# WizFiShield.net
KiCad netlist of a schematic drawn in EAGLE
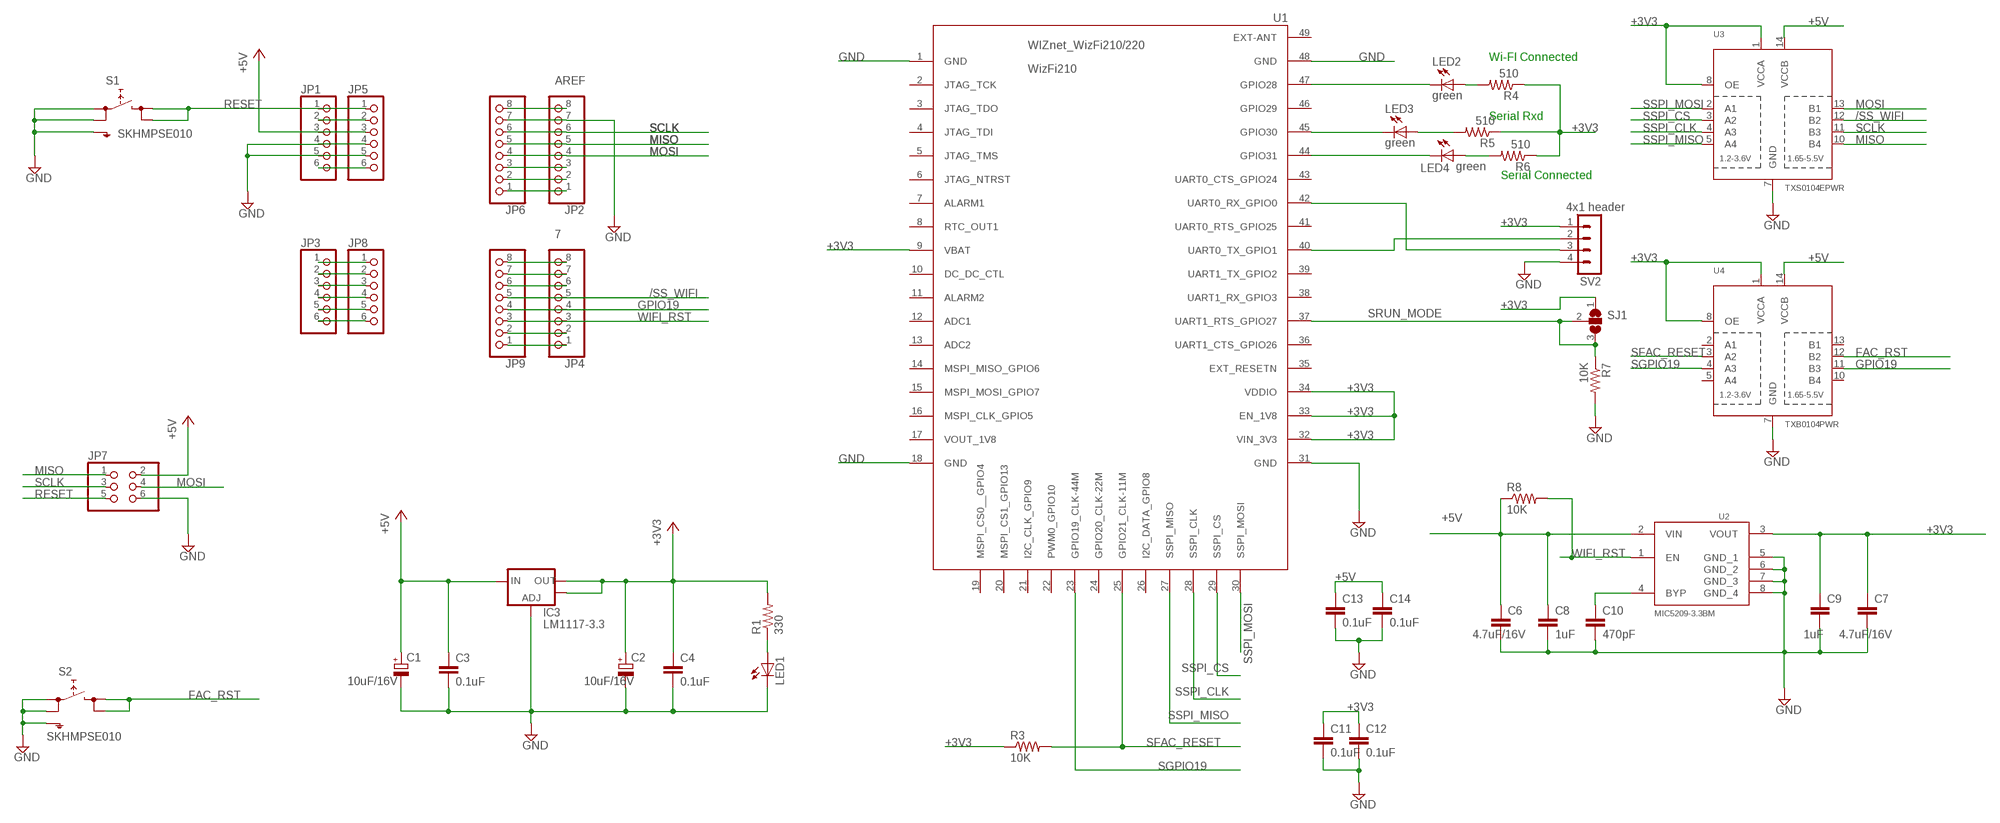
[diagram p0: schematic, sheet 1]

(export (version "E")
  (design (tool "Eeschema 10.0.6"))
  (components
    (comp (ref "C1")
      (value "10uF/16V")
      (footprint "eagle-import:CT3216")
      (libsource (lib "eagle-import") (part "CPOL-EUCT3216"))
    )
    (comp (ref "C2")
      (value "10uF/16V")
      (footprint "eagle-import:CT3216")
      (libsource (lib "eagle-import") (part "CPOL-EUCT3216"))
    )
    (comp (ref "C3")
      (value "0.1uF")
      (footprint "eagle-import:C0603")
      (libsource (lib "eagle-import") (part "C-EUC0603"))
    )
    (comp (ref "C4")
      (value "0.1uF")
      (footprint "eagle-import:C0603")
      (libsource (lib "eagle-import") (part "C-EUC0603"))
    )
    (comp (ref "C6")
      (value "4.7uF/16V")
      (footprint "eagle-import:C0805")
      (libsource (lib "eagle-import") (part "C-EUC0805"))
    )
    (comp (ref "C7")
      (value "4.7uF/16V")
      (footprint "eagle-import:C0603")
      (libsource (lib "eagle-import") (part "C-EUC0603"))
    )
    (comp (ref "C8")
      (value "1uF")
      (footprint "eagle-import:C0603")
      (libsource (lib "eagle-import") (part "C-EUC0603"))
    )
    (comp (ref "C9")
      (value "1uF")
      (footprint "eagle-import:C0805")
      (libsource (lib "eagle-import") (part "C-EUC0805"))
    )
    (comp (ref "C10")
      (value "470pF")
      (footprint "eagle-import:C0603")
      (libsource (lib "eagle-import") (part "C-EUC0603"))
    )
    (comp (ref "C11")
      (value "0.1uF")
      (footprint "eagle-import:C0603")
      (libsource (lib "eagle-import") (part "C-EUC0603"))
    )
    (comp (ref "C12")
      (value "0.1uF")
      (footprint "eagle-import:C0603")
      (libsource (lib "eagle-import") (part "C-EUC0603"))
    )
    (comp (ref "C13")
      (value "0.1uF")
      (footprint "eagle-import:C0603")
      (libsource (lib "eagle-import") (part "C-EUC0603"))
    )
    (comp (ref "C14")
      (value "0.1uF")
      (footprint "eagle-import:C0603")
      (libsource (lib "eagle-import") (part "C-EUC0603"))
    )
    (comp (ref "IC3")
      (value "LM1117-3.3")
      (footprint "eagle-import:SOT223")
      (libsource (lib "eagle-import") (part "V_REG_LM1117SOT223"))
    )
    (comp (ref "JP1")
      (value "PINHD-1X6")
      (footprint "eagle-import:1X06")
      (libsource (lib "eagle-import") (part "PINHD-1X6"))
    )
    (comp (ref "JP2")
      (value "PINHD-1X8")
      (footprint "eagle-import:1X08")
      (libsource (lib "eagle-import") (part "PINHD-1X8"))
    )
    (comp (ref "JP3")
      (value "PINHD-1X6")
      (footprint "eagle-import:1X06")
      (libsource (lib "eagle-import") (part "PINHD-1X6"))
    )
    (comp (ref "JP4")
      (value "PINHD-1X8")
      (footprint "eagle-import:1X08")
      (libsource (lib "eagle-import") (part "PINHD-1X8"))
    )
    (comp (ref "JP5")
      (value "PINHD-1X6")
      (footprint "eagle-import:1X06")
      (libsource (lib "eagle-import") (part "PINHD-1X6"))
    )
    (comp (ref "JP6")
      (value "PINHD-1X8")
      (footprint "eagle-import:1X08")
      (libsource (lib "eagle-import") (part "PINHD-1X8"))
    )
    (comp (ref "JP7")
      (value "PINHD-2X3")
      (footprint "eagle-import:2X03")
      (libsource (lib "eagle-import") (part "PINHD-2X3"))
    )
    (comp (ref "JP8")
      (value "PINHD-1X6")
      (footprint "eagle-import:1X06")
      (libsource (lib "eagle-import") (part "PINHD-1X6"))
    )
    (comp (ref "JP9")
      (value "PINHD-1X8")
      (footprint "eagle-import:1X08")
      (libsource (lib "eagle-import") (part "PINHD-1X8"))
    )
    (comp (ref "LED1")
      (value "LEDCHIP-LED0805")
      (footprint "eagle-import:CHIP-LED0805")
      (libsource (lib "eagle-import") (part "led_LEDCHIP-LED0805"))
    )
    (comp (ref "LED2")
      (value "green")
      (footprint "eagle-import:CHIP-LED0805")
      (libsource (lib "eagle-import") (part "LEDCHIP-LED0805"))
    )
    (comp (ref "LED3")
      (value "green")
      (footprint "eagle-import:CHIP-LED0805")
      (libsource (lib "eagle-import") (part "LEDCHIP-LED0805"))
    )
    (comp (ref "LED4")
      (value "green")
      (footprint "eagle-import:CHIP-LED0805")
      (libsource (lib "eagle-import") (part "LEDCHIP-LED0805"))
    )
    (comp (ref "R1")
      (value "330")
      (footprint "eagle-import:R0805")
      (libsource (lib "eagle-import") (part "R-US_R0805"))
    )
    (comp (ref "R3")
      (value "10K")
      (footprint "eagle-import:0603-RES")
      (libsource (lib "eagle-import") (part "RESISTOR0603-RES"))
    )
    (comp (ref "R4")
      (value "510")
      (footprint "eagle-import:0603-RES")
      (libsource (lib "eagle-import") (part "RESISTOR0603-RES"))
    )
    (comp (ref "R5")
      (value "510")
      (footprint "eagle-import:0603-RES")
      (libsource (lib "eagle-import") (part "RESISTOR0603-RES"))
    )
    (comp (ref "R6")
      (value "510")
      (footprint "eagle-import:0603-RES")
      (libsource (lib "eagle-import") (part "RESISTOR0603-RES"))
    )
    (comp (ref "R7")
      (value "10K")
      (footprint "eagle-import:0603-RES")
      (libsource (lib "eagle-import") (part "RESISTOR0603-RES"))
    )
    (comp (ref "R8")
      (value "10K")
      (footprint "eagle-import:0603-RES")
      (libsource (lib "eagle-import") (part "RESISTOR0603-RES"))
    )
    (comp (ref "S1")
      (value "SKHMPSE010")
      (footprint "eagle-import:SKHMPXE010")
      (libsource (lib "eagle-import") (part "SKHMPE010S"))
    )
    (comp (ref "S2")
      (value "SKHMPSE010")
      (footprint "eagle-import:SKHMPXE010")
      (libsource (lib "eagle-import") (part "SKHMPE010S"))
    )
    (comp (ref "SJ1")
      (value "SJ2W")
      (footprint "eagle-import:SJ_2")
      (libsource (lib "eagle-import") (part "SJ2W"))
    )
    (comp (ref "SV2")
      (value "4x1 header")
      (footprint "eagle-import:MA04-1")
      (libsource (lib "eagle-import") (part "MA04-1"))
    )
    (comp (ref "U1")
      (value "WizFi210")
      (footprint "eagle-import:WIZFI210_220")
      (libsource (lib "eagle-import") (part "WIZFI210/220"))
    )
    (comp (ref "U2")
      (value "MIC5209-3.3BM")
      (footprint "eagle-import:SO08")
      (libsource (lib "eagle-import") (part "MIC5209"))
    )
    (comp (ref "U3")
      (value "TXS0104EPWR")
      (footprint "eagle-import:TSSOP14")
      (libsource (lib "eagle-import") (part "TXB0104PWR"))
    )
    (comp (ref "U4")
      (value "TXB0104PWR")
      (footprint "eagle-import:TSSOP14")
      (libsource (lib "eagle-import") (part "TXB0104PWR"))
    )
  )
  (nets
    (net (code "1") (name "+3V3") (class "Default")
      (node (ref "C11") (pin "1") (pinfunction "1_1") (pintype "passive"))
      (node (ref "C12") (pin "1") (pinfunction "1_1") (pintype "passive"))
      (node (ref "C2") (pin "+") (pinfunction "+_+") (pintype "passive"))
      (node (ref "C4") (pin "1") (pinfunction "1_1") (pintype "passive"))
      (node (ref "C7") (pin "1") (pinfunction "1_1") (pintype "passive"))
      (node (ref "C9") (pin "1") (pinfunction "1_1") (pintype "passive"))
      (node (ref "IC3") (pin "2") (pinfunction "OUT_2") (pintype "output"))
      (node (ref "IC3") (pin "4") (pinfunction "OUT_4") (pintype "output"))
      (node (ref "R1") (pin "2") (pinfunction "2_2") (pintype "passive"))
      (node (ref "R3") (pin "1") (pinfunction "1_1") (pintype "passive"))
      (node (ref "R4") (pin "1") (pinfunction "1_1") (pintype "passive"))
      (node (ref "R5") (pin "1") (pinfunction "1_1") (pintype "passive"))
      (node (ref "R6") (pin "1") (pinfunction "1_1") (pintype "passive"))
      (node (ref "SJ1") (pin "1") (pinfunction "1_1") (pintype "passive"))
      (node (ref "SV2") (pin "1") (pinfunction "1_1") (pintype "passive"))
      (node (ref "U1") (pin "32") (pinfunction "VIN_3V3_32") (pintype "power_in"))
      (node (ref "U1") (pin "33") (pinfunction "EN_1V8_33") (pintype "input"))
      (node (ref "U1") (pin "34") (pinfunction "VDDIO_34") (pintype "power_in"))
      (node (ref "U1") (pin "9") (pinfunction "VBAT_9") (pintype "power_in"))
      (node (ref "U2") (pin "3") (pinfunction "VOUT_3") (pintype "output"))
      (node (ref "U3") (pin "1") (pinfunction "VCCA_1") (pintype "bidirectional"))
      (node (ref "U3") (pin "8") (pinfunction "OE_8") (pintype "bidirectional"))
      (node (ref "U4") (pin "1") (pinfunction "VCCA_1") (pintype "bidirectional"))
      (node (ref "U4") (pin "8") (pinfunction "OE_8") (pintype "bidirectional"))
    )
    (net (code "2") (name "+5V") (class "Default")
      (node (ref "C1") (pin "+") (pinfunction "+_+") (pintype "passive"))
      (node (ref "C13") (pin "1") (pinfunction "1_1") (pintype "passive"))
      (node (ref "C14") (pin "1") (pinfunction "1_1") (pintype "passive"))
      (node (ref "C3") (pin "1") (pinfunction "1_1") (pintype "passive"))
      (node (ref "C6") (pin "1") (pinfunction "1_1") (pintype "passive"))
      (node (ref "C8") (pin "1") (pinfunction "1_1") (pintype "passive"))
      (node (ref "IC3") (pin "3") (pinfunction "IN_3") (pintype "input"))
      (node (ref "JP1") (pin "3") (pinfunction "3_3") (pintype "passive"))
      (node (ref "JP5") (pin "3") (pinfunction "3_3") (pintype "passive"))
      (node (ref "JP7") (pin "2") (pinfunction "2_2") (pintype "passive"))
      (node (ref "R8") (pin "1") (pinfunction "1_1") (pintype "passive"))
      (node (ref "U2") (pin "2") (pinfunction "VIN_2") (pintype "input"))
      (node (ref "U3") (pin "14") (pinfunction "VCCB_14") (pintype "bidirectional"))
      (node (ref "U4") (pin "14") (pinfunction "VCCB_14") (pintype "bidirectional"))
    )
    (net (code "3") (name "/FAC_RST") (class "Default")
      (node (ref "S2") (pin "3") (pinfunction "2.1_3") (pintype "passive"))
      (node (ref "S2") (pin "4") (pinfunction "2.2_4") (pintype "passive"))
      (node (ref "U4") (pin "12") (pinfunction "B2_12") (pintype "bidirectional"))
    )
    (net (code "4") (name "/GPIO19") (class "Default")
      (node (ref "JP4") (pin "4") (pinfunction "4_4") (pintype "passive"))
      (node (ref "JP9") (pin "4") (pinfunction "4_4") (pintype "passive"))
      (node (ref "U4") (pin "11") (pinfunction "B3_11") (pintype "bidirectional"))
    )
    (net (code "5") (name "/MISO") (class "Default")
      (node (ref "JP2") (pin "5") (pinfunction "5_5") (pintype "passive"))
      (node (ref "JP6") (pin "5") (pinfunction "5_5") (pintype "passive"))
      (node (ref "JP7") (pin "1") (pinfunction "1_1") (pintype "passive"))
      (node (ref "U3") (pin "10") (pinfunction "B4_10") (pintype "bidirectional"))
    )
    (net (code "6") (name "/MOSI") (class "Default")
      (node (ref "JP2") (pin "4") (pinfunction "4_4") (pintype "passive"))
      (node (ref "JP6") (pin "4") (pinfunction "4_4") (pintype "passive"))
      (node (ref "JP7") (pin "4") (pinfunction "4_4") (pintype "passive"))
      (node (ref "U3") (pin "13") (pinfunction "B1_13") (pintype "bidirectional"))
    )
    (net (code "7") (name "/RESET") (class "Default")
      (node (ref "JP1") (pin "1") (pinfunction "1_1") (pintype "passive"))
      (node (ref "JP5") (pin "1") (pinfunction "1_1") (pintype "passive"))
      (node (ref "JP7") (pin "5") (pinfunction "5_5") (pintype "passive"))
      (node (ref "S1") (pin "3") (pinfunction "2.1_3") (pintype "passive"))
      (node (ref "S1") (pin "4") (pinfunction "2.2_4") (pintype "passive"))
    )
    (net (code "8") (name "/SCLK") (class "Default")
      (node (ref "JP2") (pin "6") (pinfunction "6_6") (pintype "passive"))
      (node (ref "JP6") (pin "6") (pinfunction "6_6") (pintype "passive"))
      (node (ref "JP7") (pin "3") (pinfunction "3_3") (pintype "passive"))
      (node (ref "U3") (pin "11") (pinfunction "B3_11") (pintype "bidirectional"))
    )
    (net (code "9") (name "/SFAC_RESET") (class "Default")
      (node (ref "R3") (pin "2") (pinfunction "2_2") (pintype "passive"))
      (node (ref "U1") (pin "25") (pinfunction "GPIO21_CLK-11M_25") (pintype "input"))
      (node (ref "U4") (pin "3") (pinfunction "A2_3") (pintype "bidirectional"))
    )
    (net (code "10") (name "/SGPIO19") (class "Default")
      (node (ref "U1") (pin "23") (pinfunction "GPIO19_CLK-44M_23") (pintype "input"))
      (node (ref "U4") (pin "4") (pinfunction "A3_4") (pintype "bidirectional"))
    )
    (net (code "11") (name "/SRUN_MODE") (class "Default")
      (node (ref "R7") (pin "1") (pinfunction "1_1") (pintype "passive"))
      (node (ref "SJ1") (pin "2") (pinfunction "2_2") (pintype "passive"))
      (node (ref "SJ1") (pin "3") (pinfunction "3_3") (pintype "passive"))
      (node (ref "U1") (pin "37") (pinfunction "UART1_RTS_GPIO27_37") (pintype "output"))
    )
    (net (code "12") (name "/SSPI_CLK") (class "Default")
      (node (ref "U1") (pin "28") (pinfunction "SSPI_CLK_28") (pintype "input"))
      (node (ref "U3") (pin "4") (pinfunction "A3_4") (pintype "bidirectional"))
    )
    (net (code "13") (name "/SSPI_CS") (class "Default")
      (node (ref "U1") (pin "29") (pinfunction "SSPI_CS_29") (pintype "input"))
      (node (ref "U3") (pin "3") (pinfunction "A2_3") (pintype "bidirectional"))
    )
    (net (code "14") (name "/SSPI_MISO") (class "Default")
      (node (ref "U1") (pin "27") (pinfunction "SSPI_MISO_27") (pintype "output"))
      (node (ref "U3") (pin "5") (pinfunction "A4_5") (pintype "bidirectional"))
    )
    (net (code "15") (name "/SSPI_MOSI") (class "Default")
      (node (ref "U1") (pin "30") (pinfunction "SSPI_MOSI_30") (pintype "input"))
      (node (ref "U3") (pin "2") (pinfunction "A1_2") (pintype "bidirectional"))
    )
    (net (code "16") (name "/WIFI_RST") (class "Default")
      (node (ref "JP4") (pin "3") (pinfunction "3_3") (pintype "passive"))
      (node (ref "JP9") (pin "3") (pinfunction "3_3") (pintype "passive"))
      (node (ref "R8") (pin "2") (pinfunction "2_2") (pintype "passive"))
      (node (ref "U2") (pin "1") (pinfunction "EN_1") (pintype "input"))
    )
    (net (code "17") (name "/{slash}SS_WIFI") (class "Default")
      (node (ref "JP4") (pin "5") (pinfunction "5_5") (pintype "passive"))
      (node (ref "JP9") (pin "5") (pinfunction "5_5") (pintype "passive"))
      (node (ref "U3") (pin "12") (pinfunction "B2_12") (pintype "bidirectional"))
    )
    (net (code "18") (name "GND") (class "Default")
      (node (ref "C1") (pin "-") (pinfunction "-_-") (pintype "passive"))
      (node (ref "C10") (pin "2") (pinfunction "2_2") (pintype "passive"))
      (node (ref "C11") (pin "2") (pinfunction "2_2") (pintype "passive"))
      (node (ref "C12") (pin "2") (pinfunction "2_2") (pintype "passive"))
      (node (ref "C13") (pin "2") (pinfunction "2_2") (pintype "passive"))
      (node (ref "C14") (pin "2") (pinfunction "2_2") (pintype "passive"))
      (node (ref "C2") (pin "-") (pinfunction "-_-") (pintype "passive"))
      (node (ref "C3") (pin "2") (pinfunction "2_2") (pintype "passive"))
      (node (ref "C4") (pin "2") (pinfunction "2_2") (pintype "passive"))
      (node (ref "C6") (pin "2") (pinfunction "2_2") (pintype "passive"))
      (node (ref "C7") (pin "2") (pinfunction "2_2") (pintype "passive"))
      (node (ref "C8") (pin "2") (pinfunction "2_2") (pintype "passive"))
      (node (ref "C9") (pin "2") (pinfunction "2_2") (pintype "passive"))
      (node (ref "IC3") (pin "1") (pinfunction "ADJ_1") (pintype "input"))
      (node (ref "JP1") (pin "4") (pinfunction "4_4") (pintype "passive"))
      (node (ref "JP1") (pin "5") (pinfunction "5_5") (pintype "passive"))
      (node (ref "JP2") (pin "7") (pinfunction "7_7") (pintype "passive"))
      (node (ref "JP5") (pin "4") (pinfunction "4_4") (pintype "passive"))
      (node (ref "JP5") (pin "5") (pinfunction "5_5") (pintype "passive"))
      (node (ref "JP6") (pin "7") (pinfunction "7_7") (pintype "passive"))
      (node (ref "JP7") (pin "6") (pinfunction "6_6") (pintype "passive"))
      (node (ref "LED1") (pin "C") (pinfunction "C_C") (pintype "passive"))
      (node (ref "R7") (pin "2") (pinfunction "2_2") (pintype "passive"))
      (node (ref "S1") (pin "1") (pinfunction "1.1_1") (pintype "passive"))
      (node (ref "S1") (pin "2") (pinfunction "1.2_2") (pintype "passive"))
      (node (ref "S1") (pin "5") (pinfunction "SH_5") (pintype "passive"))
      (node (ref "S2") (pin "1") (pinfunction "1.1_1") (pintype "passive"))
      (node (ref "S2") (pin "2") (pinfunction "1.2_2") (pintype "passive"))
      (node (ref "S2") (pin "5") (pinfunction "SH_5") (pintype "passive"))
      (node (ref "SV2") (pin "4") (pinfunction "4_4") (pintype "passive"))
      (node (ref "U1") (pin "1") (pinfunction "GND_1") (pintype "power_in"))
      (node (ref "U1") (pin "18") (pinfunction "GND_18") (pintype "power_in"))
      (node (ref "U1") (pin "31") (pinfunction "GND_31") (pintype "power_in"))
      (node (ref "U1") (pin "48") (pinfunction "GND_48") (pintype "power_in"))
      (node (ref "U2") (pin "5") (pinfunction "GND_1_5") (pintype "power_in"))
      (node (ref "U2") (pin "6") (pinfunction "GND_2_6") (pintype "power_in"))
      (node (ref "U2") (pin "7") (pinfunction "GND_3_7") (pintype "power_in"))
      (node (ref "U2") (pin "8") (pinfunction "GND_4_8") (pintype "power_in"))
      (node (ref "U3") (pin "7") (pinfunction "GND_7") (pintype "bidirectional"))
      (node (ref "U4") (pin "7") (pinfunction "GND_7") (pintype "bidirectional"))
    )
    (net (code "19") (name "Net-(JP1-Pad2)") (class "Default")
      (node (ref "JP1") (pin "2") (pinfunction "2_2") (pintype "passive"))
      (node (ref "JP5") (pin "2") (pinfunction "2_2") (pintype "passive"))
    )
    (net (code "20") (name "Net-(JP1-Pad6)") (class "Default")
      (node (ref "JP1") (pin "6") (pinfunction "6_6") (pintype "passive"))
      (node (ref "JP5") (pin "6") (pinfunction "6_6") (pintype "passive"))
    )
    (net (code "21") (name "Net-(JP2-Pad1)") (class "Default")
      (node (ref "JP2") (pin "1") (pinfunction "1_1") (pintype "passive"))
      (node (ref "JP6") (pin "1") (pinfunction "1_1") (pintype "passive"))
    )
    (net (code "22") (name "Net-(JP2-Pad2)") (class "Default")
      (node (ref "JP2") (pin "2") (pinfunction "2_2") (pintype "passive"))
      (node (ref "JP6") (pin "2") (pinfunction "2_2") (pintype "passive"))
    )
    (net (code "23") (name "Net-(JP2-Pad3)") (class "Default")
      (node (ref "JP2") (pin "3") (pinfunction "3_3") (pintype "passive"))
      (node (ref "JP6") (pin "3") (pinfunction "3_3") (pintype "passive"))
    )
    (net (code "24") (name "Net-(JP2-Pad8)") (class "Default")
      (node (ref "JP2") (pin "8") (pinfunction "8_8") (pintype "passive"))
      (node (ref "JP6") (pin "8") (pinfunction "8_8") (pintype "passive"))
    )
    (net (code "25") (name "Net-(JP3-Pad1)") (class "Default")
      (node (ref "JP3") (pin "1") (pinfunction "1_1") (pintype "passive"))
      (node (ref "JP8") (pin "1") (pinfunction "1_1") (pintype "passive"))
    )
    (net (code "26") (name "Net-(JP3-Pad2)") (class "Default")
      (node (ref "JP3") (pin "2") (pinfunction "2_2") (pintype "passive"))
      (node (ref "JP8") (pin "2") (pinfunction "2_2") (pintype "passive"))
    )
    (net (code "27") (name "Net-(JP3-Pad3)") (class "Default")
      (node (ref "JP3") (pin "3") (pinfunction "3_3") (pintype "passive"))
      (node (ref "JP8") (pin "3") (pinfunction "3_3") (pintype "passive"))
    )
    (net (code "28") (name "Net-(JP3-Pad4)") (class "Default")
      (node (ref "JP3") (pin "4") (pinfunction "4_4") (pintype "passive"))
      (node (ref "JP8") (pin "4") (pinfunction "4_4") (pintype "passive"))
    )
    (net (code "29") (name "Net-(JP3-Pad5)") (class "Default")
      (node (ref "JP3") (pin "5") (pinfunction "5_5") (pintype "passive"))
      (node (ref "JP8") (pin "5") (pinfunction "5_5") (pintype "passive"))
    )
    (net (code "30") (name "Net-(JP3-Pad6)") (class "Default")
      (node (ref "JP3") (pin "6") (pinfunction "6_6") (pintype "passive"))
      (node (ref "JP8") (pin "6") (pinfunction "6_6") (pintype "passive"))
    )
    (net (code "31") (name "Net-(JP4-Pad1)") (class "Default")
      (node (ref "JP4") (pin "1") (pinfunction "1_1") (pintype "passive"))
      (node (ref "JP9") (pin "1") (pinfunction "1_1") (pintype "passive"))
    )
    (net (code "32") (name "Net-(JP4-Pad2)") (class "Default")
      (node (ref "JP4") (pin "2") (pinfunction "2_2") (pintype "passive"))
      (node (ref "JP9") (pin "2") (pinfunction "2_2") (pintype "passive"))
    )
    (net (code "33") (name "Net-(JP4-Pad6)") (class "Default")
      (node (ref "JP4") (pin "6") (pinfunction "6_6") (pintype "passive"))
      (node (ref "JP9") (pin "6") (pinfunction "6_6") (pintype "passive"))
    )
    (net (code "34") (name "Net-(JP4-Pad7)") (class "Default")
      (node (ref "JP4") (pin "7") (pinfunction "7_7") (pintype "passive"))
      (node (ref "JP9") (pin "7") (pinfunction "7_7") (pintype "passive"))
    )
    (net (code "35") (name "Net-(JP4-Pad8)") (class "Default")
      (node (ref "JP4") (pin "8") (pinfunction "8_8") (pintype "passive"))
      (node (ref "JP9") (pin "8") (pinfunction "8_8") (pintype "passive"))
    )
    (net (code "36") (name "Net-(LED1-PadA)") (class "Default")
      (node (ref "LED1") (pin "A") (pinfunction "A_A") (pintype "passive"))
      (node (ref "R1") (pin "1") (pinfunction "1_1") (pintype "passive"))
    )
    (net (code "37") (name "Net-(LED2-PadA)") (class "Default")
      (node (ref "LED2") (pin "A") (pinfunction "A_A") (pintype "passive"))
      (node (ref "R4") (pin "2") (pinfunction "2_2") (pintype "passive"))
    )
    (net (code "38") (name "Net-(LED3-PadA)") (class "Default")
      (node (ref "LED3") (pin "A") (pinfunction "A_A") (pintype "passive"))
      (node (ref "R5") (pin "2") (pinfunction "2_2") (pintype "passive"))
    )
    (net (code "39") (name "Net-(LED4-PadA)") (class "Default")
      (node (ref "LED4") (pin "A") (pinfunction "A_A") (pintype "passive"))
      (node (ref "R6") (pin "2") (pinfunction "2_2") (pintype "passive"))
    )
    (net (code "40") (name "Net-(U1-GPIO28)") (class "Default")
      (node (ref "LED2") (pin "C") (pinfunction "C_C") (pintype "passive"))
      (node (ref "U1") (pin "47") (pinfunction "GPIO28_47") (pintype "bidirectional"))
    )
    (net (code "41") (name "Net-(U1-GPIO30)") (class "Default")
      (node (ref "LED3") (pin "C") (pinfunction "C_C") (pintype "passive"))
      (node (ref "U1") (pin "45") (pinfunction "GPIO30_45") (pintype "bidirectional"))
    )
    (net (code "42") (name "Net-(U1-GPIO31)") (class "Default")
      (node (ref "LED4") (pin "C") (pinfunction "C_C") (pintype "passive"))
      (node (ref "U1") (pin "44") (pinfunction "GPIO31_44") (pintype "bidirectional"))
    )
    (net (code "43") (name "Net-(U1-UART0_RX_GPIO0)") (class "Default")
      (node (ref "SV2") (pin "3") (pinfunction "3_3") (pintype "passive"))
      (node (ref "U1") (pin "42") (pinfunction "UART0_RX_GPIO0_42") (pintype "input"))
    )
    (net (code "44") (name "Net-(U1-UART0_TX_GPIO1)") (class "Default")
      (node (ref "SV2") (pin "2") (pinfunction "2_2") (pintype "passive"))
      (node (ref "U1") (pin "40") (pinfunction "UART0_TX_GPIO1_40") (pintype "output"))
    )
    (net (code "45") (name "Net-(U2-BYP)") (class "Default")
      (node (ref "C10") (pin "1") (pinfunction "1_1") (pintype "passive"))
      (node (ref "U2") (pin "4") (pinfunction "BYP_4") (pintype "input"))
    )
    (net (code "46") (name "unconnected-(U1-ADC1-Pad12)") (class "Default")
      (node (ref "U1") (pin "12") (pinfunction "ADC1_12") (pintype "input"))
    )
    (net (code "47") (name "unconnected-(U1-ADC2-Pad13)") (class "Default")
      (node (ref "U1") (pin "13") (pinfunction "ADC2_13") (pintype "input"))
    )
    (net (code "48") (name "unconnected-(U1-ALARM1-Pad7)") (class "Default")
      (node (ref "U1") (pin "7") (pinfunction "ALARM1_7") (pintype "input"))
    )
    (net (code "49") (name "unconnected-(U1-ALARM2-Pad11)") (class "Default")
      (node (ref "U1") (pin "11") (pinfunction "ALARM2_11") (pintype "input"))
    )
    (net (code "50") (name "unconnected-(U1-DC_DC_CTL-Pad10)") (class "Default")
      (node (ref "U1") (pin "10") (pinfunction "DC_DC_CTL_10") (pintype "output"))
    )
    (net (code "51") (name "unconnected-(U1-EXT-ANT-Pad49)") (class "Default")
      (node (ref "U1") (pin "49") (pinfunction "EXT-ANT_49") (pintype "bidirectional"))
    )
    (net (code "52") (name "unconnected-(U1-EXT_RESETN-Pad35)") (class "Default")
      (node (ref "U1") (pin "35") (pinfunction "EXT_RESETN_35") (pintype "bidirectional"))
    )
    (net (code "53") (name "unconnected-(U1-GPIO20_CLK-22M-Pad24)") (class "Default")
      (node (ref "U1") (pin "24") (pinfunction "GPIO20_CLK-22M_24") (pintype "input"))
    )
    (net (code "54") (name "unconnected-(U1-GPIO29-Pad46)") (class "Default")
      (node (ref "U1") (pin "46") (pinfunction "GPIO29_46") (pintype "bidirectional"))
    )
    (net (code "55") (name "unconnected-(U1-I2C_CLK_GPIO9-Pad21)") (class "Default")
      (node (ref "U1") (pin "21") (pinfunction "I2C_CLK_GPIO9_21") (pintype "bidirectional"))
    )
    (net (code "56") (name "unconnected-(U1-I2C_DATA_GPIO8-Pad26)") (class "Default")
      (node (ref "U1") (pin "26") (pinfunction "I2C_DATA_GPIO8_26") (pintype "bidirectional"))
    )
    (net (code "57") (name "unconnected-(U1-JTAG_NTRST-Pad6)") (class "Default")
      (node (ref "U1") (pin "6") (pinfunction "JTAG_NTRST_6") (pintype "input"))
    )
    (net (code "58") (name "unconnected-(U1-JTAG_TCK-Pad2)") (class "Default")
      (node (ref "U1") (pin "2") (pinfunction "JTAG_TCK_2") (pintype "input"))
    )
    (net (code "59") (name "unconnected-(U1-JTAG_TDI-Pad4)") (class "Default")
      (node (ref "U1") (pin "4") (pinfunction "JTAG_TDI_4") (pintype "input"))
    )
    (net (code "60") (name "unconnected-(U1-JTAG_TDO-Pad3)") (class "Default")
      (node (ref "U1") (pin "3") (pinfunction "JTAG_TDO_3") (pintype "output"))
    )
    (net (code "61") (name "unconnected-(U1-JTAG_TMS-Pad5)") (class "Default")
      (node (ref "U1") (pin "5") (pinfunction "JTAG_TMS_5") (pintype "input"))
    )
    (net (code "62") (name "unconnected-(U1-MSPI_CLK_GPIO5-Pad16)") (class "Default")
      (node (ref "U1") (pin "16") (pinfunction "MSPI_CLK_GPIO5_16") (pintype "bidirectional"))
    )
    (net (code "63") (name "unconnected-(U1-MSPI_CS0__GPIO4-Pad19)") (class "Default")
      (node (ref "U1") (pin "19") (pinfunction "MSPI_CS0__GPIO4_19") (pintype "output"))
    )
    (net (code "64") (name "unconnected-(U1-MSPI_CS1_GPIO13-Pad20)") (class "Default")
      (node (ref "U1") (pin "20") (pinfunction "MSPI_CS1_GPIO13_20") (pintype "output"))
    )
    (net (code "65") (name "unconnected-(U1-MSPI_MISO_GPIO6-Pad14)") (class "Default")
      (node (ref "U1") (pin "14") (pinfunction "MSPI_MISO_GPIO6_14") (pintype "input"))
    )
    (net (code "66") (name "unconnected-(U1-MSPI_MOSI_GPIO7-Pad15)") (class "Default")
      (node (ref "U1") (pin "15") (pinfunction "MSPI_MOSI_GPIO7_15") (pintype "output"))
    )
    (net (code "67") (name "unconnected-(U1-PWM0_GPIO10-Pad22)") (class "Default")
      (node (ref "U1") (pin "22") (pinfunction "PWM0_GPIO10_22") (pintype "output"))
    )
    (net (code "68") (name "unconnected-(U1-RTC_OUT1-Pad8)") (class "Default")
      (node (ref "U1") (pin "8") (pinfunction "RTC_OUT1_8") (pintype "output"))
    )
    (net (code "69") (name "unconnected-(U1-UART0_CTS_GPIO24-Pad43)") (class "Default")
      (node (ref "U1") (pin "43") (pinfunction "UART0_CTS_GPIO24_43") (pintype "input"))
    )
    (net (code "70") (name "unconnected-(U1-UART0_RTS_GPIO25-Pad41)") (class "Default")
      (node (ref "U1") (pin "41") (pinfunction "UART0_RTS_GPIO25_41") (pintype "output"))
    )
    (net (code "71") (name "unconnected-(U1-UART1_CTS_GPIO26-Pad36)") (class "Default")
      (node (ref "U1") (pin "36") (pinfunction "UART1_CTS_GPIO26_36") (pintype "input"))
    )
    (net (code "72") (name "unconnected-(U1-UART1_RX_GPIO3-Pad38)") (class "Default")
      (node (ref "U1") (pin "38") (pinfunction "UART1_RX_GPIO3_38") (pintype "input"))
    )
    (net (code "73") (name "unconnected-(U1-UART1_TX_GPIO2-Pad39)") (class "Default")
      (node (ref "U1") (pin "39") (pinfunction "UART1_TX_GPIO2_39") (pintype "output"))
    )
    (net (code "74") (name "unconnected-(U1-VOUT_1V8-Pad17)") (class "Default")
      (node (ref "U1") (pin "17") (pinfunction "VOUT_1V8_17") (pintype "bidirectional"))
    )
    (net (code "75") (name "unconnected-(U4-A1-Pad2)") (class "Default")
      (node (ref "U4") (pin "2") (pinfunction "A1_2") (pintype "bidirectional"))
    )
    (net (code "76") (name "unconnected-(U4-A4-Pad5)") (class "Default")
      (node (ref "U4") (pin "5") (pinfunction "A4_5") (pintype "bidirectional"))
    )
    (net (code "77") (name "unconnected-(U4-B1-Pad13)") (class "Default")
      (node (ref "U4") (pin "13") (pinfunction "B1_13") (pintype "bidirectional"))
    )
    (net (code "78") (name "unconnected-(U4-B4-Pad10)") (class "Default")
      (node (ref "U4") (pin "10") (pinfunction "B4_10") (pintype "bidirectional"))
    )
  )
)
